# LED_sign_Control_board_FINAL.net
KiCad netlist of a schematic drawn in EAGLE
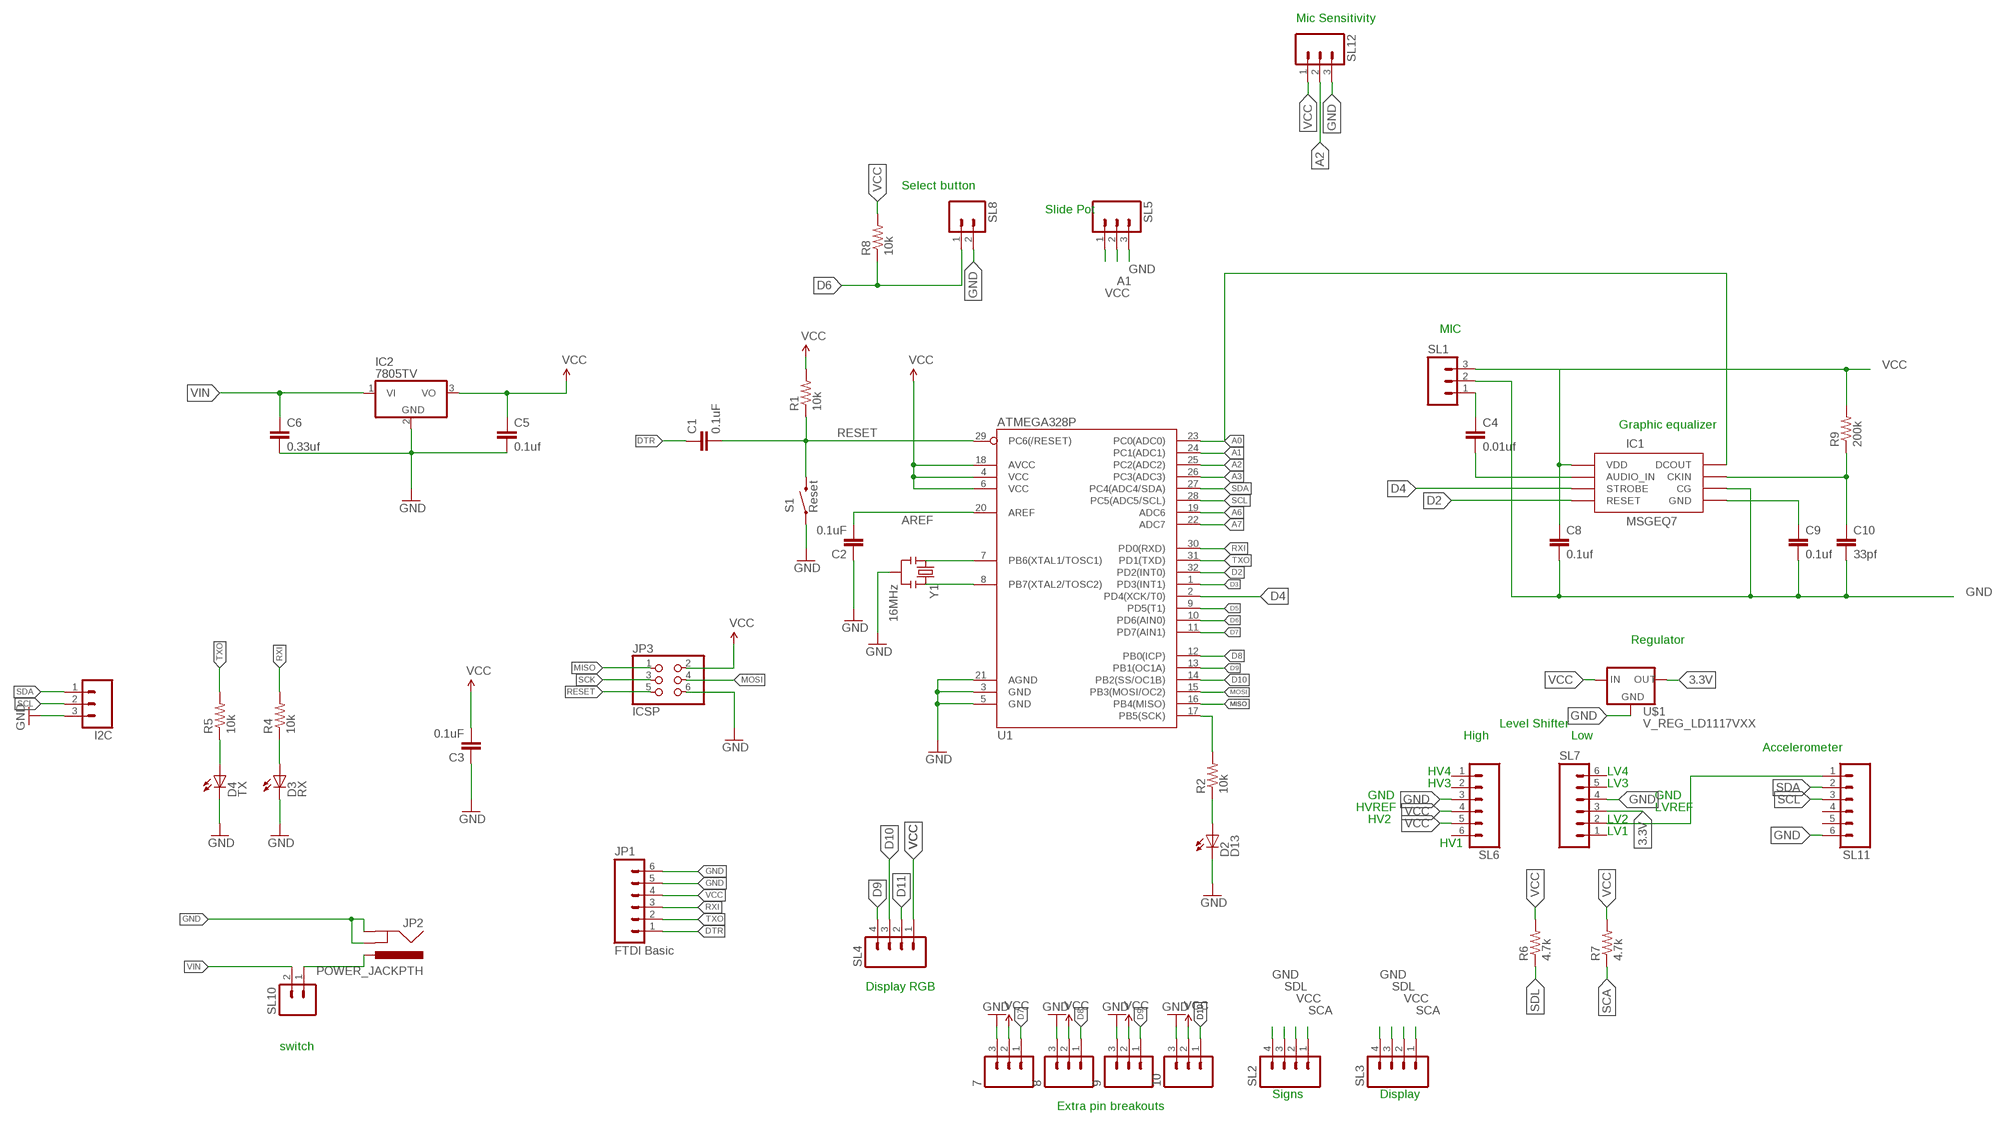
[diagram p0: schematic, sheet 1]

(export (version "E")
  (design (tool "Eeschema 10.0.6"))
  (components
    (comp (ref "7")
      (value "M03PTH")
      (footprint "eagle-import:1X03")
      (libsource (lib "eagle-import") (part "M03PTH"))
    )
    (comp (ref "8")
      (value "M03PTH")
      (footprint "eagle-import:1X03")
      (libsource (lib "eagle-import") (part "M03PTH"))
    )
    (comp (ref "9")
      (value "M03PTH")
      (footprint "eagle-import:1X03")
      (libsource (lib "eagle-import") (part "M03PTH"))
    )
    (comp (ref "10")
      (value "M03PTH")
      (footprint "eagle-import:1X03")
      (libsource (lib "eagle-import") (part "M03PTH"))
    )
    (comp (ref "C1")
      (value "0.1uF")
      (footprint "eagle-import:0603-CAP")
      (libsource (lib "eagle-import") (part "CAP0603-CAP"))
    )
    (comp (ref "C2")
      (value "0.1uF")
      (footprint "eagle-import:0603-CAP")
      (libsource (lib "eagle-import") (part "CAP0603-CAP"))
    )
    (comp (ref "C3")
      (value "0.1uF")
      (footprint "eagle-import:0603-CAP")
      (libsource (lib "eagle-import") (part "CAP0603-CAP"))
    )
    (comp (ref "C4")
      (value "0.01uf")
      (footprint "eagle-import:C2.5-3")
      (libsource (lib "eagle-import") (part "C2,5-3"))
    )
    (comp (ref "C5")
      (value "0.1uf")
      (footprint "eagle-import:C2.5-3")
      (libsource (lib "eagle-import") (part "C2,5-3"))
    )
    (comp (ref "C6")
      (value "0.33uf")
      (footprint "eagle-import:C2.5-3")
      (libsource (lib "eagle-import") (part "C2,5-3"))
    )
    (comp (ref "C8")
      (value "0.1uf")
      (footprint "eagle-import:C2.5-3")
      (libsource (lib "eagle-import") (part "C2,5-3"))
    )
    (comp (ref "C9")
      (value "0.1uf")
      (footprint "eagle-import:C2.5-3")
      (libsource (lib "eagle-import") (part "C2,5-3"))
    )
    (comp (ref "C10")
      (value "33pf")
      (footprint "eagle-import:C2.5-3")
      (libsource (lib "eagle-import") (part "C2,5-3"))
    )
    (comp (ref "D2")
      (value "D13")
      (footprint "eagle-import:LED-0603")
      (libsource (lib "eagle-import") (part "LED-RED0603"))
    )
    (comp (ref "D3")
      (value "RX")
      (footprint "eagle-import:LED-0603")
      (libsource (lib "eagle-import") (part "LED-GREEN0603"))
    )
    (comp (ref "D4")
      (value "TX")
      (footprint "eagle-import:LED-0603")
      (libsource (lib "eagle-import") (part "LED-RED0603"))
    )
    (comp (ref "I2C")
      (value "M03PTH")
      (footprint "eagle-import:1X03")
      (libsource (lib "eagle-import") (part "M03PTH"))
    )
    (comp (ref "IC1")
      (value "MSGEQ7DIL")
      (footprint "eagle-import:DIL-08")
      (libsource (lib "eagle-import") (part "MSGEQ7DIL"))
    )
    (comp (ref "IC2")
      (value "7805TV")
      (footprint "eagle-import:TO220V")
      (libsource (lib "eagle-import") (part "78TV05"))
    )
    (comp (ref "JP1")
      (value "FTDI Basic")
      (footprint "eagle-import:1X06")
      (libsource (lib "eagle-import") (part "M06SIP"))
    )
    (comp (ref "JP2")
      (value "POWER_JACKPTH")
      (footprint "eagle-import:POWER_JACK_PTH")
      (libsource (lib "eagle-import") (part "POWER_JACKPTH"))
    )
    (comp (ref "JP3")
      (value "ICSP")
      (footprint "eagle-import:2X03")
      (libsource (lib "eagle-import") (part "PINHD-2X3"))
    )
    (comp (ref "R1")
      (value "10k")
      (footprint "eagle-import:0603-RES")
      (libsource (lib "eagle-import") (part "RESISTOR0603-RES"))
    )
    (comp (ref "R2")
      (value "10k")
      (footprint "eagle-import:0603-RES")
      (libsource (lib "eagle-import") (part "RESISTOR0603-RES"))
    )
    (comp (ref "R4")
      (value "10k")
      (footprint "eagle-import:0603-RES")
      (libsource (lib "eagle-import") (part "RESISTOR0603-RES"))
    )
    (comp (ref "R5")
      (value "10k")
      (footprint "eagle-import:0603-RES")
      (libsource (lib "eagle-import") (part "RESISTOR0603-RES"))
    )
    (comp (ref "R6")
      (value "4.7k")
      (footprint "eagle-import:1206")
      (libsource (lib "eagle-import") (part "SparkFun-Resistors_RESISTOR1206"))
    )
    (comp (ref "R7")
      (value "4.7k")
      (footprint "eagle-import:1206")
      (libsource (lib "eagle-import") (part "SparkFun-Resistors_RESISTOR1206"))
    )
    (comp (ref "R8")
      (value "10k")
      (footprint "eagle-import:1206")
      (libsource (lib "eagle-import") (part "SparkFun-Resistors_RESISTOR1206"))
    )
    (comp (ref "R9")
      (value "200k")
      (footprint "eagle-import:1206")
      (libsource (lib "eagle-import") (part "SparkFun-Resistors_RESISTOR1206"))
    )
    (comp (ref "S1")
      (value "Reset")
      (footprint "eagle-import:TACTILE_SWITCH_SMD")
      (libsource (lib "eagle-import") (part "SWITCH-MOMENTARY-2SMD"))
    )
    (comp (ref "SL1")
      (value "M03")
      (footprint "eagle-import:03P")
      (libsource (lib "eagle-import") (part "M03"))
    )
    (comp (ref "SL2")
      (value "M04")
      (footprint "eagle-import:04P")
      (libsource (lib "eagle-import") (part "M04"))
    )
    (comp (ref "SL3")
      (value "M04")
      (footprint "eagle-import:04P")
      (libsource (lib "eagle-import") (part "M04"))
    )
    (comp (ref "SL4")
      (value "M04")
      (footprint "eagle-import:04P")
      (libsource (lib "eagle-import") (part "M04"))
    )
    (comp (ref "SL5")
      (value "M03")
      (footprint "eagle-import:03P")
      (libsource (lib "eagle-import") (part "M03"))
    )
    (comp (ref "SL6")
      (value "M06")
      (footprint "eagle-import:06P")
      (libsource (lib "eagle-import") (part "M06"))
    )
    (comp (ref "SL7")
      (value "M06")
      (footprint "eagle-import:06P")
      (libsource (lib "eagle-import") (part "M06"))
    )
    (comp (ref "SL8")
      (value "M02")
      (footprint "eagle-import:02P")
      (libsource (lib "eagle-import") (part "M02"))
    )
    (comp (ref "SL10")
      (value "M02")
      (footprint "eagle-import:02P")
      (libsource (lib "eagle-import") (part "M02"))
    )
    (comp (ref "SL11")
      (value "M06")
      (footprint "eagle-import:06P")
      (libsource (lib "eagle-import") (part "M06"))
    )
    (comp (ref "SL12")
      (value "M03")
      (footprint "eagle-import:03P")
      (libsource (lib "eagle-import") (part "M03"))
    )
    (comp (ref "U$1")
      (value "V_REG_LD1117VXX")
      (footprint "eagle-import:78XXL")
      (libsource (lib "eagle-import") (part "V_REG_LD1117VXX"))
    )
    (comp (ref "U1")
      (value "ATMEGA328P")
      (footprint "eagle-import:TQFP32-08")
      (libsource (lib "eagle-import") (part "ATMEGA328_SMT"))
    )
    (comp (ref "Y1")
      (value "16MHz")
      (footprint "eagle-import:RESONATOR-SMD")
      (libsource (lib "eagle-import") (part "RESONATOR16MHZ"))
    )
  )
  (nets
    (net (code "1") (name "/AREF") (class "Default")
      (node (ref "C2") (pin "2") (pinfunction "2_2") (pintype "passive"))
      (node (ref "U1") (pin "20") (pinfunction "AREF_20") (pintype "bidirectional"))
    )
    (net (code "2") (name "3.3V") (class "Default")
      (node (ref "SL7") (pin "3") (pinfunction "3_3") (pintype "passive"))
      (node (ref "U$1") (pin "GND") (pinfunction "OUT_GND") (pintype "output"))
    )
    (net (code "3") (name "A0") (class "Default")
      (node (ref "IC1") (pin "3") (pinfunction "DCOUT_3") (pintype "bidirectional"))
      (node (ref "U1") (pin "23") (pinfunction "PC0(ADC0)_23") (pintype "bidirectional"))
    )
    (net (code "4") (name "A1") (class "Default")
      (node (ref "SL5") (pin "2") (pinfunction "2_2") (pintype "passive"))
      (node (ref "U1") (pin "24") (pinfunction "PC1(ADC1)_24") (pintype "bidirectional"))
    )
    (net (code "5") (name "A2") (class "Default")
      (node (ref "SL12") (pin "2") (pinfunction "2_2") (pintype "passive"))
      (node (ref "U1") (pin "25") (pinfunction "PC2(ADC2)_25") (pintype "bidirectional"))
    )
    (net (code "6") (name "A3") (class "Default")
      (node (ref "U1") (pin "26") (pinfunction "PC3(ADC3)_26") (pintype "bidirectional"))
    )
    (net (code "7") (name "A6") (class "Default")
      (node (ref "U1") (pin "19") (pinfunction "ADC6_19") (pintype "bidirectional"))
    )
    (net (code "8") (name "A7") (class "Default")
      (node (ref "U1") (pin "22") (pinfunction "ADC7_22") (pintype "bidirectional"))
    )
    (net (code "9") (name "D2") (class "Default")
      (node (ref "IC1") (pin "7") (pinfunction "RESET_7") (pintype "input"))
      (node (ref "U1") (pin "32") (pinfunction "PD2(INT0)_32") (pintype "bidirectional"))
    )
    (net (code "10") (name "D3") (class "Default")
      (node (ref "U1") (pin "1") (pinfunction "PD3(INT1)_1") (pintype "bidirectional"))
    )
    (net (code "11") (name "D4") (class "Default")
      (node (ref "IC1") (pin "4") (pinfunction "STROBE_4") (pintype "input"))
      (node (ref "U1") (pin "2") (pinfunction "PD4(XCK/T0)_2") (pintype "bidirectional"))
    )
    (net (code "12") (name "D5") (class "Default")
      (node (ref "U1") (pin "9") (pinfunction "PD5(T1)_9") (pintype "bidirectional"))
    )
    (net (code "13") (name "D6") (class "Default")
      (node (ref "R8") (pin "1") (pinfunction "1_1") (pintype "passive"))
      (node (ref "SL8") (pin "1") (pinfunction "1_1") (pintype "passive"))
      (node (ref "U1") (pin "10") (pinfunction "PD6(AIN0)_10") (pintype "bidirectional"))
    )
    (net (code "14") (name "D7") (class "Default")
      (node (ref "7") (pin "1") (pinfunction "1_1") (pintype "passive"))
      (node (ref "U1") (pin "11") (pinfunction "PD7(AIN1)_11") (pintype "bidirectional"))
    )
    (net (code "15") (name "D8") (class "Default")
      (node (ref "8") (pin "1") (pinfunction "1_1") (pintype "passive"))
      (node (ref "U1") (pin "12") (pinfunction "PB0(ICP)_12") (pintype "bidirectional"))
    )
    (net (code "16") (name "D9") (class "Default")
      (node (ref "9") (pin "1") (pinfunction "1_1") (pintype "passive"))
      (node (ref "SL4") (pin "4") (pinfunction "4_4") (pintype "passive"))
      (node (ref "U1") (pin "13") (pinfunction "PB1(OC1A)_13") (pintype "bidirectional"))
    )
    (net (code "17") (name "D10") (class "Default")
      (node (ref "10") (pin "1") (pinfunction "1_1") (pintype "passive"))
      (node (ref "SL4") (pin "3") (pinfunction "3_3") (pintype "passive"))
      (node (ref "U1") (pin "14") (pinfunction "PB2(SS/OC1B)_14") (pintype "bidirectional"))
    )
    (net (code "18") (name "D11") (class "Default")
      (node (ref "SL4") (pin "2") (pinfunction "2_2") (pintype "passive"))
    )
    (net (code "19") (name "DTR") (class "Default")
      (node (ref "C1") (pin "1") (pinfunction "1_1") (pintype "passive"))
      (node (ref "JP1") (pin "1") (pinfunction "1_1") (pintype "passive"))
    )
    (net (code "20") (name "GND") (class "Default")
      (node (ref "10") (pin "3") (pinfunction "3_3") (pintype "passive"))
      (node (ref "7") (pin "3") (pinfunction "3_3") (pintype "passive"))
      (node (ref "8") (pin "3") (pinfunction "3_3") (pintype "passive"))
      (node (ref "9") (pin "3") (pinfunction "3_3") (pintype "passive"))
      (node (ref "C10") (pin "2") (pinfunction "2_2") (pintype "passive"))
      (node (ref "C2") (pin "1") (pinfunction "1_1") (pintype "passive"))
      (node (ref "C3") (pin "1") (pinfunction "1_1") (pintype "passive"))
      (node (ref "C5") (pin "2") (pinfunction "2_2") (pintype "passive"))
      (node (ref "C6") (pin "2") (pinfunction "2_2") (pintype "passive"))
      (node (ref "C8") (pin "2") (pinfunction "2_2") (pintype "passive"))
      (node (ref "C9") (pin "2") (pinfunction "2_2") (pintype "passive"))
      (node (ref "D2") (pin "C") (pinfunction "C_C") (pintype "passive"))
      (node (ref "D3") (pin "C") (pinfunction "C_C") (pintype "passive"))
      (node (ref "D4") (pin "C") (pinfunction "C_C") (pintype "passive"))
      (node (ref "I2C") (pin "3") (pinfunction "3_3") (pintype "passive"))
      (node (ref "IC1") (pin "6") (pinfunction "CG_6") (pintype "bidirectional"))
      (node (ref "IC2") (pin "2") (pinfunction "GND_2") (pintype "passive"))
      (node (ref "JP1") (pin "5") (pinfunction "5_5") (pintype "passive"))
      (node (ref "JP1") (pin "6") (pinfunction "6_6") (pintype "passive"))
      (node (ref "JP2") (pin "GND") (pinfunction "GND_GND") (pintype "bidirectional"))
      (node (ref "JP2") (pin "GNDBREAK") (pinfunction "GNDBREAK_GNDBREAK") (pintype "bidirectional"))
      (node (ref "JP3") (pin "6") (pinfunction "6_6") (pintype "passive"))
      (node (ref "S1") (pin "1") (pinfunction "1_1") (pintype "passive"))
      (node (ref "SL1") (pin "2") (pinfunction "2_2") (pintype "passive"))
      (node (ref "SL11") (pin "6") (pinfunction "6_6") (pintype "passive"))
      (node (ref "SL12") (pin "3") (pinfunction "3_3") (pintype "passive"))
      (node (ref "SL2") (pin "4") (pinfunction "4_4") (pintype "passive"))
      (node (ref "SL3") (pin "4") (pinfunction "4_4") (pintype "passive"))
      (node (ref "SL5") (pin "3") (pinfunction "3_3") (pintype "passive"))
      (node (ref "SL6") (pin "3") (pinfunction "3_3") (pintype "passive"))
      (node (ref "SL7") (pin "4") (pinfunction "4_4") (pintype "passive"))
      (node (ref "SL8") (pin "2") (pinfunction "2_2") (pintype "passive"))
      (node (ref "U$1") (pin "IN") (pinfunction "GND_IN") (pintype "input"))
      (node (ref "U1") (pin "21") (pinfunction "AGND_21") (pintype "bidirectional"))
      (node (ref "U1") (pin "3") (pinfunction "GND_3") (pintype "bidirectional"))
      (node (ref "U1") (pin "5") (pinfunction "GND_5") (pintype "bidirectional"))
      (node (ref "Y1") (pin "2") (pinfunction "2_2") (pintype "passive"))
    )
    (net (code "21") (name "MISO") (class "Default")
      (node (ref "JP3") (pin "1") (pinfunction "1_1") (pintype "passive"))
      (node (ref "U1") (pin "16") (pinfunction "PB4(MISO)_16") (pintype "bidirectional"))
    )
    (net (code "22") (name "MOSI") (class "Default")
      (node (ref "JP3") (pin "4") (pinfunction "4_4") (pintype "passive"))
      (node (ref "U1") (pin "15") (pinfunction "PB3(MOSI/OC2)_15") (pintype "bidirectional"))
    )
    (net (code "23") (name "Net-(C4-Pad1)") (class "Default")
      (node (ref "C4") (pin "1") (pinfunction "1_1") (pintype "passive"))
      (node (ref "SL1") (pin "1") (pinfunction "1_1") (pintype "passive"))
    )
    (net (code "24") (name "Net-(D2-PadA)") (class "Default")
      (node (ref "D2") (pin "A") (pinfunction "A_A") (pintype "passive"))
      (node (ref "R2") (pin "1") (pinfunction "1_1") (pintype "passive"))
    )
    (net (code "25") (name "Net-(D3-PadA)") (class "Default")
      (node (ref "D3") (pin "A") (pinfunction "A_A") (pintype "passive"))
      (node (ref "R4") (pin "1") (pinfunction "1_1") (pintype "passive"))
    )
    (net (code "26") (name "Net-(D4-PadA)") (class "Default")
      (node (ref "D4") (pin "A") (pinfunction "A_A") (pintype "passive"))
      (node (ref "R5") (pin "1") (pinfunction "1_1") (pintype "passive"))
    )
    (net (code "27") (name "Net-(IC1-AUDIO_IN)") (class "Default")
      (node (ref "C4") (pin "2") (pinfunction "2_2") (pintype "passive"))
      (node (ref "IC1") (pin "5") (pinfunction "AUDIO_IN_5") (pintype "input"))
    )
    (net (code "28") (name "Net-(IC1-CKIN)") (class "Default")
      (node (ref "C10") (pin "1") (pinfunction "1_1") (pintype "passive"))
      (node (ref "IC1") (pin "8") (pinfunction "CKIN_8") (pintype "bidirectional"))
      (node (ref "R9") (pin "1") (pinfunction "1_1") (pintype "passive"))
    )
    (net (code "29") (name "Net-(IC1-GND)") (class "Default")
      (node (ref "C9") (pin "1") (pinfunction "1_1") (pintype "passive"))
      (node (ref "IC1") (pin "2") (pinfunction "GND_2") (pintype "bidirectional"))
    )
    (net (code "30") (name "Net-(JP2-PadPWR)") (class "Default")
      (node (ref "JP2") (pin "PWR") (pinfunction "PWR_PWR") (pintype "bidirectional"))
      (node (ref "SL10") (pin "1") (pinfunction "1_1") (pintype "passive"))
    )
    (net (code "31") (name "Net-(SL11-Pad1)") (class "Default")
      (node (ref "SL11") (pin "1") (pinfunction "1_1") (pintype "passive"))
      (node (ref "SL7") (pin "2") (pinfunction "2_2") (pintype "passive"))
    )
    (net (code "32") (name "Net-(U1-PB5(SCK))") (class "Default")
      (node (ref "R2") (pin "2") (pinfunction "2_2") (pintype "passive"))
      (node (ref "U1") (pin "17") (pinfunction "PB5(SCK)_17") (pintype "bidirectional"))
    )
    (net (code "33") (name "Net-(U1-PB6(XTAL1{slash}TOSC1))") (class "Default")
      (node (ref "U1") (pin "7") (pinfunction "PB6(XTAL1/TOSC1)_7") (pintype "bidirectional"))
      (node (ref "Y1") (pin "1") (pinfunction "1_1") (pintype "passive"))
    )
    (net (code "34") (name "Net-(U1-PB7(XTAL2{slash}TOSC2))") (class "Default")
      (node (ref "U1") (pin "8") (pinfunction "PB7(XTAL2/TOSC2)_8") (pintype "bidirectional"))
      (node (ref "Y1") (pin "3") (pinfunction "3_3") (pintype "passive"))
    )
    (net (code "35") (name "RESET") (class "Default")
      (node (ref "C1") (pin "2") (pinfunction "2_2") (pintype "passive"))
      (node (ref "JP3") (pin "5") (pinfunction "5_5") (pintype "passive"))
      (node (ref "R1") (pin "1") (pinfunction "1_1") (pintype "passive"))
      (node (ref "S1") (pin "3") (pinfunction "2_3") (pintype "passive"))
      (node (ref "U1") (pin "29") (pinfunction "PC6(/RESET)_29") (pintype "bidirectional"))
    )
    (net (code "36") (name "RXI") (class "Default")
      (node (ref "JP1") (pin "3") (pinfunction "3_3") (pintype "passive"))
      (node (ref "R4") (pin "2") (pinfunction "2_2") (pintype "passive"))
      (node (ref "U1") (pin "30") (pinfunction "PD0(RXD)_30") (pintype "bidirectional"))
    )
    (net (code "37") (name "SCA") (class "Default")
      (node (ref "R7") (pin "1") (pinfunction "1_1") (pintype "passive"))
      (node (ref "SL2") (pin "1") (pinfunction "1_1") (pintype "passive"))
      (node (ref "SL3") (pin "1") (pinfunction "1_1") (pintype "passive"))
    )
    (net (code "38") (name "SCK") (class "Default")
      (node (ref "JP3") (pin "3") (pinfunction "3_3") (pintype "passive"))
    )
    (net (code "39") (name "SCL") (class "Default")
      (node (ref "I2C") (pin "2") (pinfunction "2_2") (pintype "passive"))
      (node (ref "SL11") (pin "3") (pinfunction "3_3") (pintype "passive"))
      (node (ref "U1") (pin "28") (pinfunction "PC5(ADC5/SCL)_28") (pintype "bidirectional"))
    )
    (net (code "40") (name "SDA") (class "Default")
      (node (ref "I2C") (pin "1") (pinfunction "1_1") (pintype "passive"))
      (node (ref "SL11") (pin "2") (pinfunction "2_2") (pintype "passive"))
      (node (ref "U1") (pin "27") (pinfunction "PC4(ADC4/SDA)_27") (pintype "bidirectional"))
    )
    (net (code "41") (name "SDL") (class "Default")
      (node (ref "R6") (pin "1") (pinfunction "1_1") (pintype "passive"))
      (node (ref "SL2") (pin "3") (pinfunction "3_3") (pintype "passive"))
      (node (ref "SL3") (pin "3") (pinfunction "3_3") (pintype "passive"))
    )
    (net (code "42") (name "TXO") (class "Default")
      (node (ref "JP1") (pin "2") (pinfunction "2_2") (pintype "passive"))
      (node (ref "R5") (pin "2") (pinfunction "2_2") (pintype "passive"))
      (node (ref "U1") (pin "31") (pinfunction "PD1(TXD)_31") (pintype "bidirectional"))
    )
    (net (code "43") (name "VCC") (class "Default")
      (node (ref "10") (pin "2") (pinfunction "2_2") (pintype "passive"))
      (node (ref "7") (pin "2") (pinfunction "2_2") (pintype "passive"))
      (node (ref "8") (pin "2") (pinfunction "2_2") (pintype "passive"))
      (node (ref "9") (pin "2") (pinfunction "2_2") (pintype "passive"))
      (node (ref "C3") (pin "2") (pinfunction "2_2") (pintype "passive"))
      (node (ref "C5") (pin "1") (pinfunction "1_1") (pintype "passive"))
      (node (ref "C8") (pin "1") (pinfunction "1_1") (pintype "passive"))
      (node (ref "IC1") (pin "1") (pinfunction "VDD_1") (pintype "input"))
      (node (ref "IC2") (pin "3") (pinfunction "VO_3") (pintype "passive"))
      (node (ref "JP1") (pin "4") (pinfunction "4_4") (pintype "passive"))
      (node (ref "JP3") (pin "2") (pinfunction "2_2") (pintype "passive"))
      (node (ref "R1") (pin "2") (pinfunction "2_2") (pintype "passive"))
      (node (ref "R6") (pin "2") (pinfunction "2_2") (pintype "passive"))
      (node (ref "R7") (pin "2") (pinfunction "2_2") (pintype "passive"))
      (node (ref "R8") (pin "2") (pinfunction "2_2") (pintype "passive"))
      (node (ref "R9") (pin "2") (pinfunction "2_2") (pintype "passive"))
      (node (ref "SL1") (pin "3") (pinfunction "3_3") (pintype "passive"))
      (node (ref "SL12") (pin "1") (pinfunction "1_1") (pintype "passive"))
      (node (ref "SL2") (pin "2") (pinfunction "2_2") (pintype "passive"))
      (node (ref "SL3") (pin "2") (pinfunction "2_2") (pintype "passive"))
      (node (ref "SL4") (pin "1") (pinfunction "1_1") (pintype "passive"))
      (node (ref "SL5") (pin "1") (pinfunction "1_1") (pintype "passive"))
      (node (ref "SL6") (pin "4") (pinfunction "4_4") (pintype "passive"))
      (node (ref "SL6") (pin "5") (pinfunction "5_5") (pintype "passive"))
      (node (ref "U$1") (pin "OUT") (pinfunction "IN_OUT") (pintype "input"))
      (node (ref "U1") (pin "18") (pinfunction "AVCC_18") (pintype "bidirectional"))
      (node (ref "U1") (pin "4") (pinfunction "VCC_4") (pintype "bidirectional"))
      (node (ref "U1") (pin "6") (pinfunction "VCC_6") (pintype "bidirectional"))
    )
    (net (code "44") (name "VIN") (class "Default")
      (node (ref "C6") (pin "1") (pinfunction "1_1") (pintype "passive"))
      (node (ref "IC2") (pin "1") (pinfunction "VI_1") (pintype "input"))
      (node (ref "SL10") (pin "2") (pinfunction "2_2") (pintype "passive"))
    )
    (net (code "45") (name "unconnected-(SL6-Pad1)") (class "Default")
      (node (ref "SL6") (pin "1") (pinfunction "1_1") (pintype "passive"))
    )
    (net (code "46") (name "unconnected-(SL6-Pad2)") (class "Default")
      (node (ref "SL6") (pin "2") (pinfunction "2_2") (pintype "passive"))
    )
    (net (code "47") (name "unconnected-(SL6-Pad6)") (class "Default")
      (node (ref "SL6") (pin "6") (pinfunction "6_6") (pintype "passive"))
    )
    (net (code "48") (name "unconnected-(SL7-Pad1)") (class "Default")
      (node (ref "SL7") (pin "1") (pinfunction "1_1") (pintype "passive"))
    )
    (net (code "49") (name "unconnected-(SL7-Pad5)") (class "Default")
      (node (ref "SL7") (pin "5") (pinfunction "5_5") (pintype "passive"))
    )
    (net (code "50") (name "unconnected-(SL7-Pad6)") (class "Default")
      (node (ref "SL7") (pin "6") (pinfunction "6_6") (pintype "passive"))
    )
    (net (code "51") (name "unconnected-(SL11-Pad4)") (class "Default")
      (node (ref "SL11") (pin "4") (pinfunction "4_4") (pintype "passive"))
    )
    (net (code "52") (name "unconnected-(SL11-Pad5)") (class "Default")
      (node (ref "SL11") (pin "5") (pinfunction "5_5") (pintype "passive"))
    )
  )
)
